# DSP.net
KiCad netlist of a schematic drawn in Altium Designer
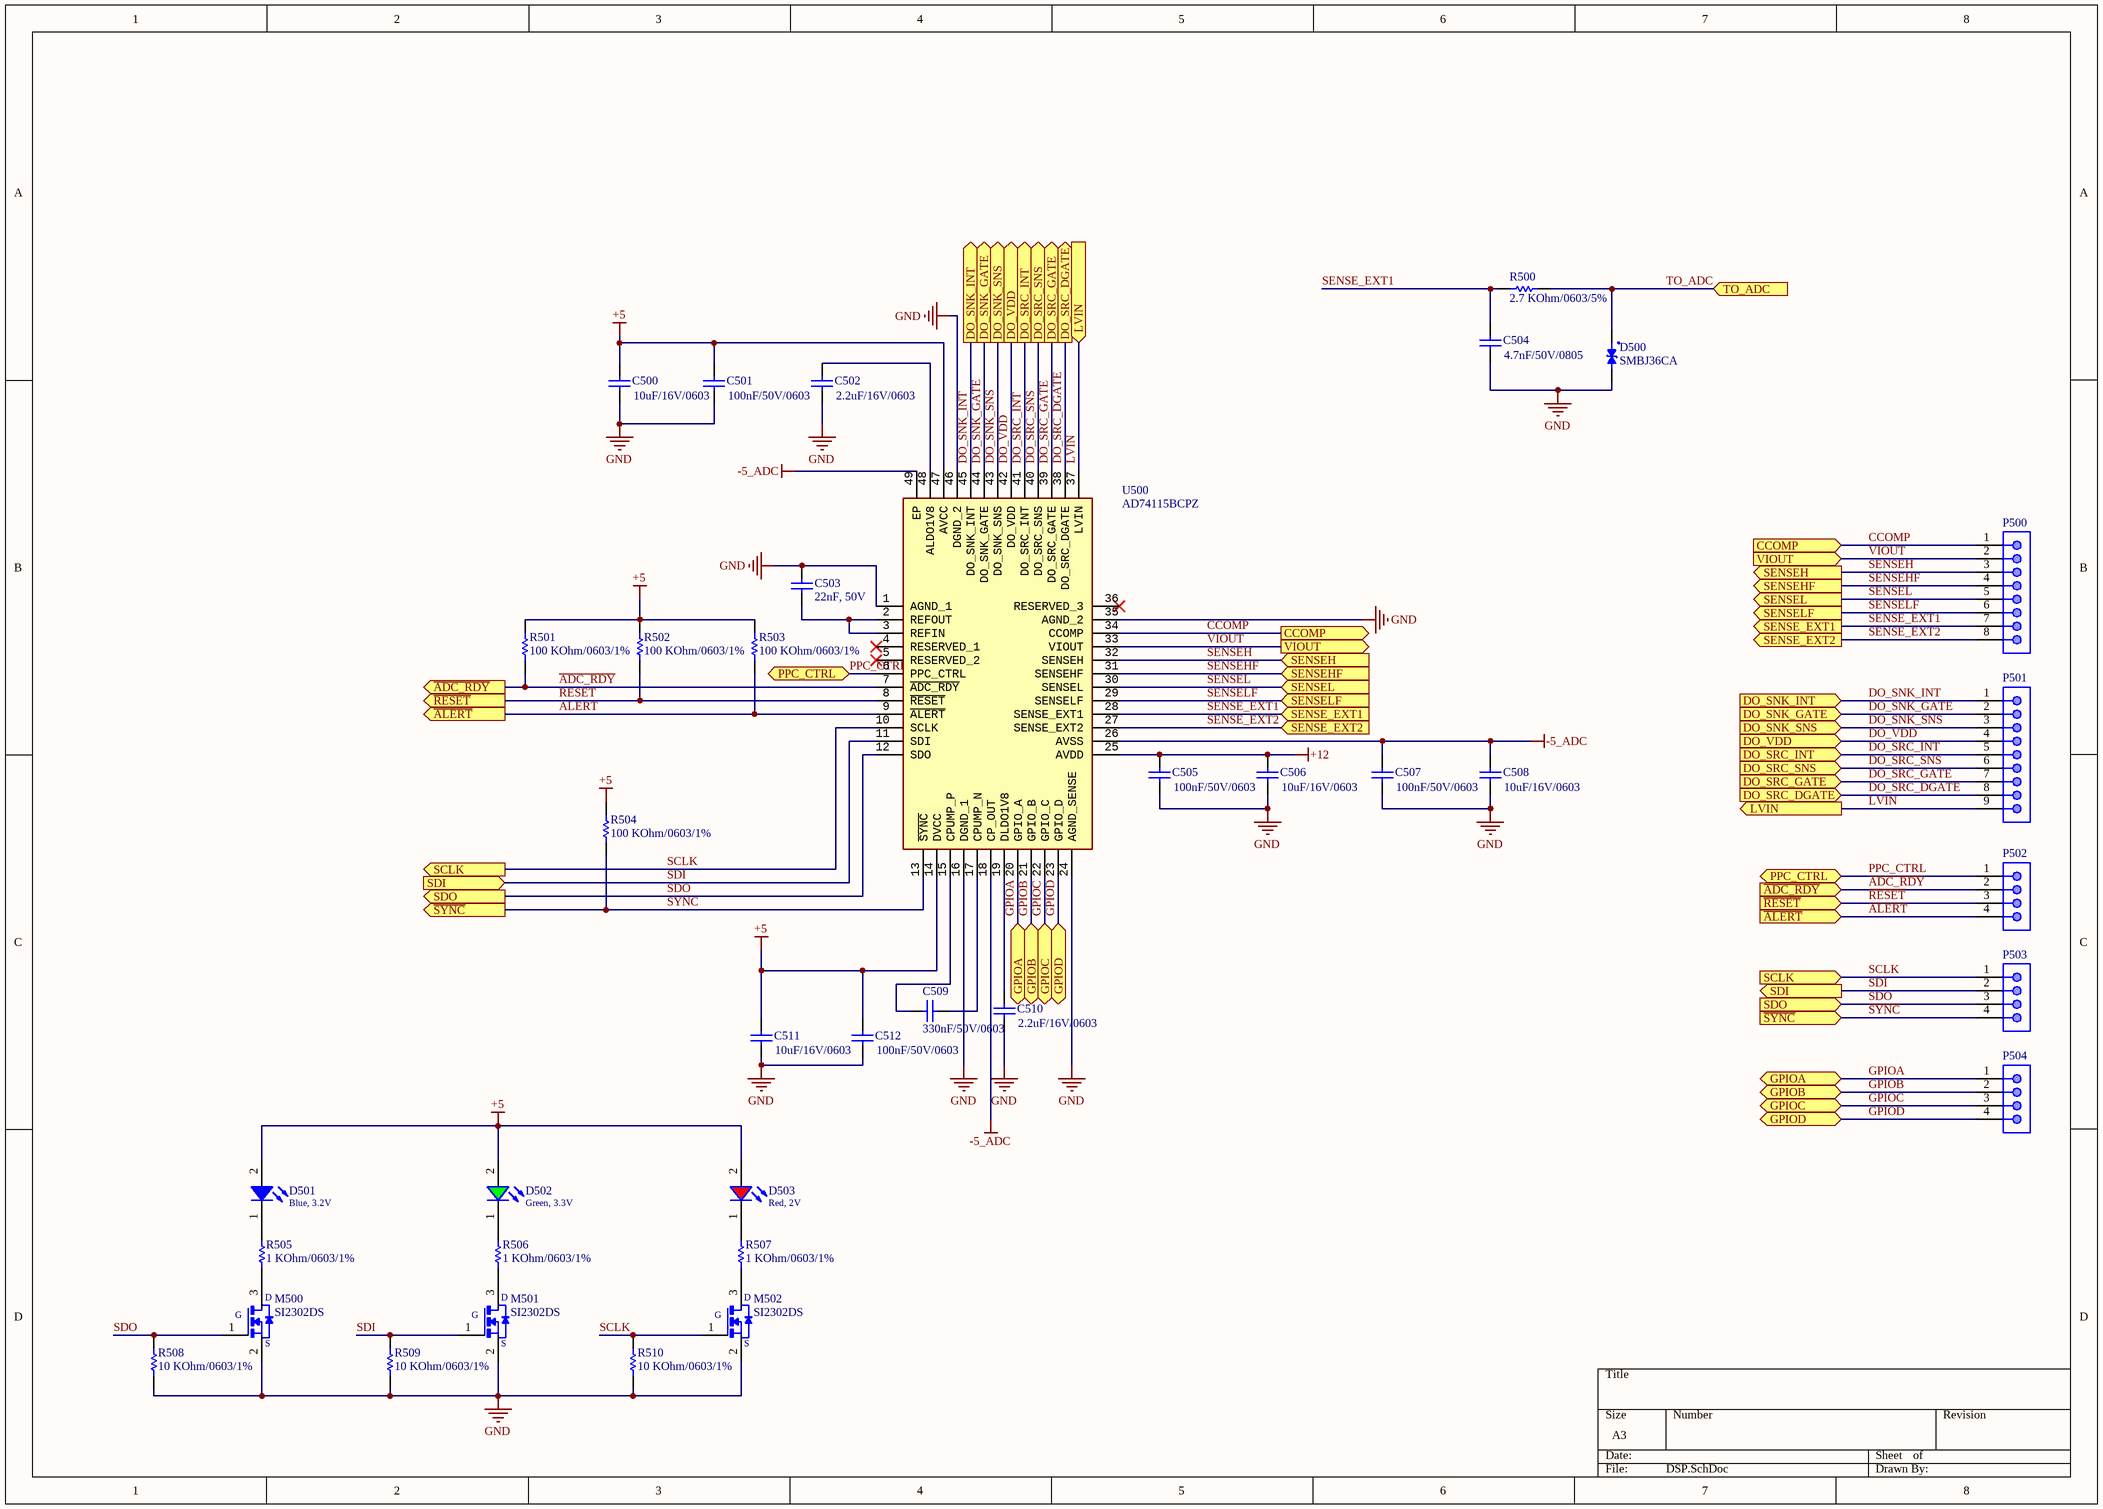
[diagram p0: DSP.SchDoc]

(export (version "E")
  (design (tool "Eeschema 10.0.6"))
  (components
    (comp (ref "C500")
      (value "10uF/16V/0603")
      (footprint "WCAP-CSGP_0603_H=0.8mm_Reflow")
      (description "WCAP-CSGP Multilayer Ceramic Chip Capacitor, General Purpose, size 0603, X5R, 10uF, 6.3V")
      (fields
        (field (name "MANUFACTURER PART NUMBER") "885012106006")
        (field (name "MANUFACTURER") "Wurth Elektronik")
      )
      (libsource (lib "Altium_WCAP-CSGP (rev20a)") (part "885012106006"))
    )
    (comp (ref "C501")
      (value "100nF, 50V")
      (footprint "WCAP-CSGP_0603_H=0.8mm_Reflow")
      (description "WCAP-CSGP Multilayer Ceramic Chip Capacitor, General Purpose, size 0603, X7R, 100nF, 50V")
      (fields
        (field (name "MANUFACTURER PART NUMBER") "885012206095")
        (field (name "MANUFACTURER") "Wurth Elektronik")
        (field (name "CAPACITANCE") "100nF/50V/0603")
      )
      (libsource (lib "Altium_WCAP-CSGP (rev20a)") (part "885012206095"))
    )
    (comp (ref "C502")
      (value "2.2uF/16V/0603")
      (footprint "WCAP-CSGP_0603_H=0.8mm_Reflow")
      (description "WCAP-CSGP Multilayer Ceramic Chip Capacitor, General Purpose, size 0603, X5R, 2.2uF, 16V")
      (fields
        (field (name "MANUFACTURER PART NUMBER") "885012106018")
        (field (name "MANUFACTURER") "Wurth Elektronik")
      )
      (libsource (lib "Altium_WCAP-CSGP (rev20a)") (part "885012106018"))
    )
    (comp (ref "C503")
      (value "22nF, 50V")
      (footprint "WCAP-CSGP_0603_H=0.8mm_Reflow")
      (description "WCAP-CSGP Multilayer Ceramic Chip Capacitor, General Purpose, size 0603, X7R, 22nF, 50V")
      (fields
        (field (name "MANUFACTURER PART NUMBER") "885012206091")
        (field (name "MANUFACTURER") "Wurth Elektronik")
      )
      (libsource (lib "Altium_WCAP-CSGP (rev20a)") (part "885012206091"))
    )
    (comp (ref "C504")
      (value "4.7nF, 100V")
      (footprint "WCAP-CSGP_0805_H=1.25mm")
      (description "WCAP-CSGP Multilayer Ceramic Chip Capacitor, General Purpose, size 0805, NP0, 4.7nF, 100V")
      (fields
        (field (name "MANUFACTURER PART NUMBER") "885012007092")
        (field (name "MANUFACTURER") "Wurth Elektronik")
        (field (name "CAPACITANCE") "4.7nF/50V/0805")
      )
      (libsource (lib "Altium_WCAP-CSGP (rev20a)") (part "885012007092"))
    )
    (comp (ref "C505")
      (value "100nF, 50V")
      (footprint "WCAP-CSGP_0603_H=0.8mm_Reflow")
      (description "WCAP-CSGP Multilayer Ceramic Chip Capacitor, General Purpose, size 0603, X7R, 100nF, 50V")
      (fields
        (field (name "MANUFACTURER PART NUMBER") "885012206095")
        (field (name "MANUFACTURER") "Wurth Elektronik")
        (field (name "CAPACITANCE") "100nF/50V/0603")
      )
      (libsource (lib "Altium_WCAP-CSGP (rev20a)") (part "885012206095"))
    )
    (comp (ref "C506")
      (value "10uF/16V/0603")
      (footprint "WCAP-CSGP_0603_H=0.8mm_Reflow")
      (description "WCAP-CSGP Multilayer Ceramic Chip Capacitor, General Purpose, size 0603, X5R, 10uF, 6.3V")
      (fields
        (field (name "MANUFACTURER PART NUMBER") "885012106006")
        (field (name "MANUFACTURER") "Wurth Elektronik")
      )
      (libsource (lib "Altium_WCAP-CSGP (rev20a)") (part "885012106006"))
    )
    (comp (ref "C507")
      (value "100nF, 50V")
      (footprint "WCAP-CSGP_0603_H=0.8mm_Reflow")
      (description "WCAP-CSGP Multilayer Ceramic Chip Capacitor, General Purpose, size 0603, X7R, 100nF, 50V")
      (fields
        (field (name "MANUFACTURER PART NUMBER") "885012206095")
        (field (name "MANUFACTURER") "Wurth Elektronik")
        (field (name "CAPACITANCE") "100nF/50V/0603")
      )
      (libsource (lib "Altium_WCAP-CSGP (rev20a)") (part "885012206095"))
    )
    (comp (ref "C508")
      (value "10uF/16V/0603")
      (footprint "WCAP-CSGP_0603_H=0.8mm_Reflow")
      (description "WCAP-CSGP Multilayer Ceramic Chip Capacitor, General Purpose, size 0603, X5R, 10uF, 6.3V")
      (fields
        (field (name "MANUFACTURER PART NUMBER") "885012106006")
        (field (name "MANUFACTURER") "Wurth Elektronik")
      )
      (libsource (lib "Altium_WCAP-CSGP (rev20a)") (part "885012106006"))
    )
    (comp (ref "C509")
      (value "330nF/50V/0603")
      (footprint "WCAP-CSGP_0603_H=0.8mm_Reflow")
      (description "WCAP-CSGP Multilayer Ceramic Chip Capacitor, General Purpose, size 0603, X7R, 330nF, 50V")
      (fields
        (field (name "MANUFACTURER PART NUMBER") "885012206121")
        (field (name "MANUFACTURER") "Wurth Elektronik")
      )
      (libsource (lib "Altium_WCAP-CSGP (rev20a)") (part "885012206121"))
    )
    (comp (ref "C510")
      (value "2.2uF/16V/0603")
      (footprint "WCAP-CSGP_0603_H=0.8mm_Reflow")
      (description "WCAP-CSGP Multilayer Ceramic Chip Capacitor, General Purpose, size 0603, X5R, 2.2uF, 16V")
      (fields
        (field (name "MANUFACTURER PART NUMBER") "885012106018")
        (field (name "MANUFACTURER") "Wurth Elektronik")
      )
      (libsource (lib "Altium_WCAP-CSGP (rev20a)") (part "885012106018"))
    )
    (comp (ref "C511")
      (value "10uF/16V/0603")
      (footprint "WCAP-CSGP_0603_H=0.8mm_Reflow")
      (description "WCAP-CSGP Multilayer Ceramic Chip Capacitor, General Purpose, size 0603, X5R, 10uF, 6.3V")
      (fields
        (field (name "MANUFACTURER PART NUMBER") "885012106006")
        (field (name "MANUFACTURER") "Wurth Elektronik")
      )
      (libsource (lib "Altium_WCAP-CSGP (rev20a)") (part "885012106006"))
    )
    (comp (ref "C512")
      (value "100nF, 50V")
      (footprint "WCAP-CSGP_0603_H=0.8mm_Reflow")
      (description "WCAP-CSGP Multilayer Ceramic Chip Capacitor, General Purpose, size 0603, X7R, 100nF, 50V")
      (fields
        (field (name "MANUFACTURER PART NUMBER") "885012206095")
        (field (name "MANUFACTURER") "Wurth Elektronik")
        (field (name "CAPACITANCE") "100nF/50V/0603")
      )
      (libsource (lib "Altium_WCAP-CSGP (rev20a)") (part "885012206095"))
    )
    (comp (ref "D500")
      (value "SMBJ36CA")
      (footprint "DIOM4336X265N")
      (description "600W, 42.1V, 5%, Bidirectional, TVS")
      (fields (field (name "MF") "Taiwan Semiconductor"))
      (libsource (lib "Giang's Libs") (part "SMBJ36CA"))
    )
    (comp (ref "D501")
      (value "Blue, 3.2V")
      (footprint "WL-SMCW_0603 dome")
      (description "WL-SMCW SMT Mono-color Chip LED Waterclear, size 0603 dome, Blue, 3.2V, 40deg")
      (fields (field (name "PART NUMBER") "150060BS84000") (field (name "PUBLISHER") "Wurth Elektronik"))
      (libsource (lib "Altium_WL-SMCW (rev20a)") (part "150060BS84000"))
    )
    (comp (ref "D502")
      (value "Green, 3.3V")
      (footprint "WL-SMCW_0603 dome")
      (description "WL-SMCW SMT Mono-color Chip LED Waterclear, size 0603 dome, Green, 3.3V, 40deg")
      (fields (field (name "PART NUMBER") "150060GS84000") (field (name "PUBLISHER") "Wurth Elektronik"))
      (libsource (lib "Altium_WL-SMCW (rev20a)") (part "150060GS84000"))
    )
    (comp (ref "D503")
      (value "Red, 2V")
      (footprint "WL-SMCW_0603 dome")
      (description "WL-SMCW SMT Mono-color Chip LED Waterclear, size 0603 dome, Red, 2V, 60deg")
      (fields (field (name "PART NUMBER") "150060RS86000") (field (name "PUBLISHER") "Wurth Elektronik"))
      (libsource (lib "Altium_WL-SMCW (rev20a)") (part "150060RS86000"))
    )
    (comp (ref "M500")
      (value "SI2302DS")
      (footprint "SOT23")
      (description "N-Channel 20 V 2.6A (Ta) 710mW (Ta) Surface Mount SOT-23-3 (TO-236)")
      (fields (field (name "MP") "SI2302") (field (name "MF") "Vishay Siliconix"))
      (libsource (lib "Giang_Transistor") (part "SI2302"))
    )
    (comp (ref "M501")
      (value "SI2302DS")
      (footprint "SOT23")
      (description "N-Channel 20 V 2.6A (Ta) 710mW (Ta) Surface Mount SOT-23-3 (TO-236)")
      (fields (field (name "MP") "SI2302") (field (name "MF") "Vishay Siliconix"))
      (libsource (lib "Giang_Transistor") (part "SI2302"))
    )
    (comp (ref "M502")
      (value "SI2302DS")
      (footprint "SOT23")
      (description "N-Channel 20 V 2.6A (Ta) 710mW (Ta) Surface Mount SOT-23-3 (TO-236)")
      (fields (field (name "MP") "SI2302") (field (name "MF") "Vishay Siliconix"))
      (libsource (lib "Giang_Transistor") (part "SI2302"))
    )
    (comp (ref "P500")
      (value "61300811121")
      (footprint "61300811121")
      (description "WR-PHD Pin Header, THT, pitch 2.54mm, Single Row, Vertical, 8p")
      (fields (field (name "MANUFACTURER") "Wurth Elektronik"))
      (libsource (lib "Altium_WR-PHD (rev20a)") (part "61300811121"))
    )
    (comp (ref "P501")
      (value "61300911121")
      (footprint "61300911121")
      (description "WR-PHD Pin Header, THT, pitch 2.54mm, Single Row, Vertical, 9p")
      (fields (field (name "MANUFACTURER") "Wurth Elektronik"))
      (libsource (lib "Altium_WR-PHD (rev20a)") (part "61300911121"))
    )
    (comp (ref "P502")
      (value "61300411121")
      (footprint "61300411121")
      (description "WR-PHD Pin Header, THT, pitch 2.54mm, Single Row, Vertical, 4p")
      (fields (field (name "MANUFACTURER") "Wurth Elektronik"))
      (libsource (lib "Altium_WR-PHD (rev20a)") (part "61300411121"))
    )
    (comp (ref "P503")
      (value "61300411121")
      (footprint "61300411121")
      (description "WR-PHD Pin Header, THT, pitch 2.54mm, Single Row, Vertical, 4p")
      (fields (field (name "MANUFACTURER") "Wurth Elektronik"))
      (libsource (lib "Altium_WR-PHD (rev20a)") (part "61300411121"))
    )
    (comp (ref "P504")
      (value "61300411121")
      (footprint "61300411121")
      (description "WR-PHD Pin Header, THT, pitch 2.54mm, Single Row, Vertical, 4p")
      (fields (field (name "MANUFACTURER") "Wurth Elektronik"))
      (libsource (lib "Altium_WR-PHD (rev20a)") (part "61300411121"))
    )
    (comp (ref "R500")
      (value "2.7 KOhm/0603/5%")
      (footprint "R0603")
      (description "Code 272, 1/10W")
      (fields (field (name "Comment") "Resistor 2.7 KOhm 0603 5%"))
      (libsource (lib "Giang_Resistor") (part "Resistor 2.7 KOhm 0603 5%"))
    )
    (comp (ref "R501")
      (value "100 KOhm/0603/1%")
      (footprint "R0603")
      (description "Code 104, 1/10W")
      (fields (field (name "Comment") "Resistor 100 KOhm 0603 1%"))
      (libsource (lib "Giang_Resistor") (part "Resistor 100 KOhm 0603 1%"))
    )
    (comp (ref "R502")
      (value "100 KOhm/0603/1%")
      (footprint "R0603")
      (description "Code 104, 1/10W")
      (fields (field (name "Comment") "Resistor 100 KOhm 0603 1%"))
      (libsource (lib "Giang_Resistor") (part "Resistor 100 KOhm 0603 1%"))
    )
    (comp (ref "R503")
      (value "100 KOhm/0603/1%")
      (footprint "R0603")
      (description "Code 104, 1/10W")
      (fields (field (name "Comment") "Resistor 100 KOhm 0603 1%"))
      (libsource (lib "Giang_Resistor") (part "Resistor 100 KOhm 0603 1%"))
    )
    (comp (ref "R504")
      (value "100 KOhm/0603/1%")
      (footprint "R0603")
      (description "Code 104, 1/10W")
      (fields (field (name "Comment") "Resistor 100 KOhm 0603 1%"))
      (libsource (lib "Giang_Resistor") (part "Resistor 100 KOhm 0603 1%"))
    )
    (comp (ref "R505")
      (value "1 KOhm/0603/1%")
      (footprint "R0603")
      (description "Code 102, 1/10W")
      (fields (field (name "Comment") "Resistor 1 KOhm 0603 1%"))
      (libsource (lib "Giang_Resistor") (part "Resistor 1 KOhm 0603 1%"))
    )
    (comp (ref "R506")
      (value "1 KOhm/0603/1%")
      (footprint "R0603")
      (description "Code 102, 1/10W")
      (fields (field (name "Comment") "Resistor 1 KOhm 0603 1%"))
      (libsource (lib "Giang_Resistor") (part "Resistor 1 KOhm 0603 1%"))
    )
    (comp (ref "R507")
      (value "1 KOhm/0603/1%")
      (footprint "R0603")
      (description "Code 102, 1/10W")
      (fields (field (name "Comment") "Resistor 1 KOhm 0603 1%"))
      (libsource (lib "Giang_Resistor") (part "Resistor 1 KOhm 0603 1%"))
    )
    (comp (ref "R508")
      (value "10 KOhm/0603/1%")
      (footprint "R0603")
      (description "Code 103, 1/10W")
      (fields (field (name "Comment") "Resistor 10 KOhm 0603 1%"))
      (libsource (lib "Giang_Resistor") (part "Resistor 10 KOhm 0603 1%"))
    )
    (comp (ref "R509")
      (value "10 KOhm/0603/1%")
      (footprint "R0603")
      (description "Code 103, 1/10W")
      (fields (field (name "Comment") "Resistor 10 KOhm 0603 1%"))
      (libsource (lib "Giang_Resistor") (part "Resistor 10 KOhm 0603 1%"))
    )
    (comp (ref "R510")
      (value "10 KOhm/0603/1%")
      (footprint "R0603")
      (description "Code 103, 1/10W")
      (fields (field (name "Comment") "Resistor 10 KOhm 0603 1%"))
      (libsource (lib "Giang_Resistor") (part "Resistor 10 KOhm 0603 1%"))
    )
    (comp (ref "U500")
      (value "AD74115BCPZ")
      (footprint "QFN50P700X700X80-49N-D")
      (description "Single-Channel, Software Configurable Input and Output")
      (fields (field (name "MOUSER PART NUMBER") "584-AD74115BCPZ"))
      (libsource (lib "Giang's Libs") (part "AD74115BCPZ"))
    )
  )
  (nets
    (net (code "1") (name "+5") (class "Default")
      (node (ref "C500") (pin "2") (pinfunction "2_2") (pintype "passive"))
      (node (ref "C501") (pin "2") (pinfunction "2_2") (pintype "passive"))
      (node (ref "C511") (pin "2") (pinfunction "2_2") (pintype "passive"))
      (node (ref "C512") (pin "2") (pinfunction "2_2") (pintype "passive"))
      (node (ref "D501") (pin "2") (pinfunction "A_2") (pintype "passive"))
      (node (ref "D502") (pin "2") (pinfunction "A_2") (pintype "passive"))
      (node (ref "D503") (pin "2") (pinfunction "A_2") (pintype "passive"))
      (node (ref "R501") (pin "2") (pinfunction "2_2") (pintype "passive"))
      (node (ref "R502") (pin "2") (pinfunction "2_2") (pintype "passive"))
      (node (ref "R503") (pin "2") (pinfunction "2_2") (pintype "passive"))
      (node (ref "R504") (pin "1") (pinfunction "1_1") (pintype "passive"))
      (node (ref "U500") (pin "14") (pinfunction "DVCC_14") (pintype "passive"))
      (node (ref "U500") (pin "47") (pinfunction "AVCC_47") (pintype "passive"))
    )
    (net (code "2") (name "+12") (class "Default")
      (node (ref "C505") (pin "2") (pinfunction "2_2") (pintype "passive"))
      (node (ref "C506") (pin "2") (pinfunction "2_2") (pintype "passive"))
      (node (ref "U500") (pin "25") (pinfunction "AVDD_25") (pintype "passive"))
    )
    (net (code "3") (name "-5_ADC") (class "Default")
      (node (ref "C507") (pin "2") (pinfunction "2_2") (pintype "passive"))
      (node (ref "C508") (pin "2") (pinfunction "2_2") (pintype "passive"))
      (node (ref "U500") (pin "18") (pinfunction "CP_OUT_18") (pintype "passive"))
      (node (ref "U500") (pin "26") (pinfunction "AVSS_26") (pintype "passive"))
      (node (ref "U500") (pin "49") (pinfunction "EP_49") (pintype "passive"))
    )
    (net (code "4") (name "/CCOMP") (class "Default")
      (node (ref "P500") (pin "1") (pinfunction "1_1") (pintype "passive"))
      (node (ref "U500") (pin "34") (pinfunction "CCOMP_34") (pintype "passive"))
    )
    (net (code "5") (name "/DO_SNK_GATE") (class "Default")
      (node (ref "P501") (pin "2") (pinfunction "2_2") (pintype "passive"))
      (node (ref "U500") (pin "44") (pinfunction "DO_SNK_GATE_44") (pintype "passive"))
    )
    (net (code "6") (name "/DO_SNK_INT") (class "Default")
      (node (ref "P501") (pin "1") (pinfunction "1_1") (pintype "passive"))
      (node (ref "U500") (pin "45") (pinfunction "DO_SNK_INT_45") (pintype "passive"))
    )
    (net (code "7") (name "/DO_SNK_SNS") (class "Default")
      (node (ref "P501") (pin "3") (pinfunction "3_3") (pintype "passive"))
      (node (ref "U500") (pin "43") (pinfunction "DO_SNK_SNS_43") (pintype "passive"))
    )
    (net (code "8") (name "/DO_SRC_DGATE") (class "Default")
      (node (ref "P501") (pin "8") (pinfunction "8_8") (pintype "passive"))
      (node (ref "U500") (pin "38") (pinfunction "DO_SRC_DGATE_38") (pintype "passive"))
    )
    (net (code "9") (name "/DO_SRC_GATE") (class "Default")
      (node (ref "P501") (pin "7") (pinfunction "7_7") (pintype "passive"))
      (node (ref "U500") (pin "39") (pinfunction "DO_SRC_GATE_39") (pintype "passive"))
    )
    (net (code "10") (name "/DO_SRC_INT") (class "Default")
      (node (ref "P501") (pin "5") (pinfunction "5_5") (pintype "passive"))
      (node (ref "U500") (pin "41") (pinfunction "DO_SRC_INT_41") (pintype "passive"))
    )
    (net (code "11") (name "/DO_SRC_SNS") (class "Default")
      (node (ref "P501") (pin "6") (pinfunction "6_6") (pintype "passive"))
      (node (ref "U500") (pin "40") (pinfunction "DO_SRC_SNS_40") (pintype "passive"))
    )
    (net (code "12") (name "/DO_VDD") (class "Default")
      (node (ref "P501") (pin "4") (pinfunction "4_4") (pintype "passive"))
      (node (ref "U500") (pin "42") (pinfunction "DO_VDD_42") (pintype "passive"))
    )
    (net (code "13") (name "/GPIOA") (class "Default")
      (node (ref "P504") (pin "1") (pinfunction "1_1") (pintype "passive"))
      (node (ref "U500") (pin "20") (pinfunction "GPIO_A_20") (pintype "passive"))
    )
    (net (code "14") (name "/GPIOB") (class "Default")
      (node (ref "P504") (pin "2") (pinfunction "2_2") (pintype "passive"))
      (node (ref "U500") (pin "21") (pinfunction "GPIO_B_21") (pintype "passive"))
    )
    (net (code "15") (name "/GPIOC") (class "Default")
      (node (ref "P504") (pin "3") (pinfunction "3_3") (pintype "passive"))
      (node (ref "U500") (pin "22") (pinfunction "GPIO_C_22") (pintype "passive"))
    )
    (net (code "16") (name "/GPIOD") (class "Default")
      (node (ref "P504") (pin "4") (pinfunction "4_4") (pintype "passive"))
      (node (ref "U500") (pin "23") (pinfunction "GPIO_D_23") (pintype "passive"))
    )
    (net (code "17") (name "/LVIN") (class "Default")
      (node (ref "P501") (pin "9") (pinfunction "9_9") (pintype "passive"))
      (node (ref "U500") (pin "37") (pinfunction "LVIN_37") (pintype "passive"))
    )
    (net (code "18") (name "/PPC_CTRL") (class "Default")
      (node (ref "P502") (pin "1") (pinfunction "1_1") (pintype "passive"))
      (node (ref "U500") (pin "6") (pinfunction "PPC_CTRL_6") (pintype "passive"))
    )
    (net (code "19") (name "/SCLK") (class "Default")
      (node (ref "M502") (pin "1") (pinfunction "G_1") (pintype "passive"))
      (node (ref "P503") (pin "1") (pinfunction "1_1") (pintype "passive"))
      (node (ref "R510") (pin "2") (pinfunction "2_2") (pintype "passive"))
      (node (ref "U500") (pin "10") (pinfunction "SCLK_10") (pintype "passive"))
    )
    (net (code "20") (name "/SDI") (class "Default")
      (node (ref "M501") (pin "1") (pinfunction "G_1") (pintype "passive"))
      (node (ref "P503") (pin "2") (pinfunction "2_2") (pintype "passive"))
      (node (ref "R509") (pin "2") (pinfunction "2_2") (pintype "passive"))
      (node (ref "U500") (pin "11") (pinfunction "SDI_11") (pintype "passive"))
    )
    (net (code "21") (name "/SDO") (class "Default")
      (node (ref "M500") (pin "1") (pinfunction "G_1") (pintype "passive"))
      (node (ref "P503") (pin "3") (pinfunction "3_3") (pintype "passive"))
      (node (ref "R508") (pin "2") (pinfunction "2_2") (pintype "passive"))
      (node (ref "U500") (pin "12") (pinfunction "SDO_12") (pintype "passive"))
    )
    (net (code "22") (name "/SENSEH") (class "Default")
      (node (ref "P500") (pin "3") (pinfunction "3_3") (pintype "passive"))
      (node (ref "U500") (pin "32") (pinfunction "SENSEH_32") (pintype "passive"))
    )
    (net (code "23") (name "/SENSEHF") (class "Default")
      (node (ref "P500") (pin "4") (pinfunction "4_4") (pintype "passive"))
      (node (ref "U500") (pin "31") (pinfunction "SENSEHF_31") (pintype "passive"))
    )
    (net (code "24") (name "/SENSEL") (class "Default")
      (node (ref "P500") (pin "5") (pinfunction "5_5") (pintype "passive"))
      (node (ref "U500") (pin "30") (pinfunction "SENSEL_30") (pintype "passive"))
    )
    (net (code "25") (name "/SENSELF") (class "Default")
      (node (ref "P500") (pin "6") (pinfunction "6_6") (pintype "passive"))
      (node (ref "U500") (pin "29") (pinfunction "SENSELF_29") (pintype "passive"))
    )
    (net (code "26") (name "/SENSE_EXT1") (class "Default")
      (node (ref "C504") (pin "2") (pinfunction "2_2") (pintype "passive"))
      (node (ref "P500") (pin "7") (pinfunction "7_7") (pintype "passive"))
      (node (ref "R500") (pin "1") (pinfunction "1_1") (pintype "passive"))
      (node (ref "U500") (pin "28") (pinfunction "SENSE_EXT1_28") (pintype "passive"))
    )
    (net (code "27") (name "/SENSE_EXT2") (class "Default")
      (node (ref "P500") (pin "8") (pinfunction "8_8") (pintype "passive"))
      (node (ref "U500") (pin "27") (pinfunction "SENSE_EXT2_27") (pintype "passive"))
    )
    (net (code "28") (name "/TO_ADC") (class "Default")
      (node (ref "D500") (pin "1") (pinfunction "1_1") (pintype "passive"))
      (node (ref "R500") (pin "2") (pinfunction "2_2") (pintype "passive"))
    )
    (net (code "29") (name "/VIOUT") (class "Default")
      (node (ref "P500") (pin "2") (pinfunction "2_2") (pintype "passive"))
      (node (ref "U500") (pin "33") (pinfunction "VIOUT_33") (pintype "passive"))
    )
    (net (code "30") (name "/~{ADC_RDY}") (class "Default")
      (node (ref "P502") (pin "2") (pinfunction "2_2") (pintype "passive"))
      (node (ref "R501") (pin "1") (pinfunction "1_1") (pintype "passive"))
      (node (ref "U500") (pin "7") (pinfunction "~{ADC_RDY}_7") (pintype "passive"))
    )
    (net (code "31") (name "/~{ALERT}") (class "Default")
      (node (ref "P502") (pin "4") (pinfunction "4_4") (pintype "passive"))
      (node (ref "R503") (pin "1") (pinfunction "1_1") (pintype "passive"))
      (node (ref "U500") (pin "9") (pinfunction "~{ALERT}_9") (pintype "passive"))
    )
    (net (code "32") (name "/~{RESET}") (class "Default")
      (node (ref "P502") (pin "3") (pinfunction "3_3") (pintype "passive"))
      (node (ref "R502") (pin "1") (pinfunction "1_1") (pintype "passive"))
      (node (ref "U500") (pin "8") (pinfunction "~{RESET}_8") (pintype "passive"))
    )
    (net (code "33") (name "/~{SYNC}") (class "Default")
      (node (ref "P503") (pin "4") (pinfunction "4_4") (pintype "passive"))
      (node (ref "R504") (pin "2") (pinfunction "2_2") (pintype "passive"))
      (node (ref "U500") (pin "13") (pinfunction "~{SYNC}_13") (pintype "passive"))
    )
    (net (code "34") (name "GND") (class "Default")
      (node (ref "C500") (pin "1") (pinfunction "1_1") (pintype "passive"))
      (node (ref "C501") (pin "1") (pinfunction "1_1") (pintype "passive"))
      (node (ref "C502") (pin "1") (pinfunction "1_1") (pintype "passive"))
      (node (ref "C503") (pin "2") (pinfunction "2_2") (pintype "passive"))
      (node (ref "C504") (pin "1") (pinfunction "1_1") (pintype "passive"))
      (node (ref "C505") (pin "1") (pinfunction "1_1") (pintype "passive"))
      (node (ref "C506") (pin "1") (pinfunction "1_1") (pintype "passive"))
      (node (ref "C507") (pin "1") (pinfunction "1_1") (pintype "passive"))
      (node (ref "C508") (pin "1") (pinfunction "1_1") (pintype "passive"))
      (node (ref "C510") (pin "1") (pinfunction "1_1") (pintype "passive"))
      (node (ref "C511") (pin "1") (pinfunction "1_1") (pintype "passive"))
      (node (ref "C512") (pin "1") (pinfunction "1_1") (pintype "passive"))
      (node (ref "D500") (pin "2") (pinfunction "2_2") (pintype "passive"))
      (node (ref "M500") (pin "2") (pinfunction "S_2") (pintype "passive"))
      (node (ref "M501") (pin "2") (pinfunction "S_2") (pintype "passive"))
      (node (ref "M502") (pin "2") (pinfunction "S_2") (pintype "passive"))
      (node (ref "R508") (pin "1") (pinfunction "1_1") (pintype "passive"))
      (node (ref "R509") (pin "1") (pinfunction "1_1") (pintype "passive"))
      (node (ref "R510") (pin "1") (pinfunction "1_1") (pintype "passive"))
      (node (ref "U500") (pin "1") (pinfunction "AGND_1_1") (pintype "passive"))
      (node (ref "U500") (pin "16") (pinfunction "DGND_1_16") (pintype "passive"))
      (node (ref "U500") (pin "24") (pinfunction "AGND_SENSE_24") (pintype "passive"))
      (node (ref "U500") (pin "35") (pinfunction "AGND_2_35") (pintype "passive"))
      (node (ref "U500") (pin "46") (pinfunction "DGND_2_46") (pintype "passive"))
    )
    (net (code "35") (name "Net-(D501-K)") (class "Default")
      (node (ref "D501") (pin "1") (pinfunction "K_1") (pintype "passive"))
      (node (ref "R505") (pin "2") (pinfunction "2_2") (pintype "passive"))
    )
    (net (code "36") (name "Net-(D502-K)") (class "Default")
      (node (ref "D502") (pin "1") (pinfunction "K_1") (pintype "passive"))
      (node (ref "R506") (pin "2") (pinfunction "2_2") (pintype "passive"))
    )
    (net (code "37") (name "Net-(D503-K)") (class "Default")
      (node (ref "D503") (pin "1") (pinfunction "K_1") (pintype "passive"))
      (node (ref "R507") (pin "2") (pinfunction "2_2") (pintype "passive"))
    )
    (net (code "38") (name "Net-(M500-D)") (class "Default")
      (node (ref "M500") (pin "3") (pinfunction "D_3") (pintype "passive"))
      (node (ref "R505") (pin "1") (pinfunction "1_1") (pintype "passive"))
    )
    (net (code "39") (name "Net-(M501-D)") (class "Default")
      (node (ref "M501") (pin "3") (pinfunction "D_3") (pintype "passive"))
      (node (ref "R506") (pin "1") (pinfunction "1_1") (pintype "passive"))
    )
    (net (code "40") (name "Net-(M502-D)") (class "Default")
      (node (ref "M502") (pin "3") (pinfunction "D_3") (pintype "passive"))
      (node (ref "R507") (pin "1") (pinfunction "1_1") (pintype "passive"))
    )
    (net (code "41") (name "Net-(U500-ALDO1V8)") (class "Default")
      (node (ref "C502") (pin "2") (pinfunction "2_2") (pintype "passive"))
      (node (ref "U500") (pin "48") (pinfunction "ALDO1V8_48") (pintype "passive"))
    )
    (net (code "42") (name "Net-(U500-CPUMP_N)") (class "Default")
      (node (ref "C509") (pin "1") (pinfunction "1_1") (pintype "passive"))
      (node (ref "U500") (pin "17") (pinfunction "CPUMP_N_17") (pintype "passive"))
    )
    (net (code "43") (name "Net-(U500-CPUMP_P)") (class "Default")
      (node (ref "C509") (pin "2") (pinfunction "2_2") (pintype "passive"))
      (node (ref "U500") (pin "15") (pinfunction "CPUMP_P_15") (pintype "passive"))
    )
    (net (code "44") (name "Net-(U500-DLDO1V8)") (class "Default")
      (node (ref "C510") (pin "2") (pinfunction "2_2") (pintype "passive"))
      (node (ref "U500") (pin "19") (pinfunction "DLDO1V8_19") (pintype "passive"))
    )
    (net (code "45") (name "Net-(U500-REFIN)") (class "Default")
      (node (ref "C503") (pin "1") (pinfunction "1_1") (pintype "passive"))
      (node (ref "U500") (pin "2") (pinfunction "REFOUT_2") (pintype "passive"))
      (node (ref "U500") (pin "3") (pinfunction "REFIN_3") (pintype "passive"))
    )
    (net (code "46") (name "unconnected-(U500-RESERVED_1-Pad4)") (class "Default")
      (node (ref "U500") (pin "4") (pinfunction "RESERVED_1_4") (pintype "passive+no_connect"))
    )
    (net (code "47") (name "unconnected-(U500-RESERVED_2-Pad5)") (class "Default")
      (node (ref "U500") (pin "5") (pinfunction "RESERVED_2_5") (pintype "passive+no_connect"))
    )
    (net (code "48") (name "unconnected-(U500-RESERVED_3-Pad36)") (class "Default")
      (node (ref "U500") (pin "36") (pinfunction "RESERVED_3_36") (pintype "passive+no_connect"))
    )
  )
)
